# USB_Connectors.net
KiCad netlist of a schematic drawn in Altium Designer
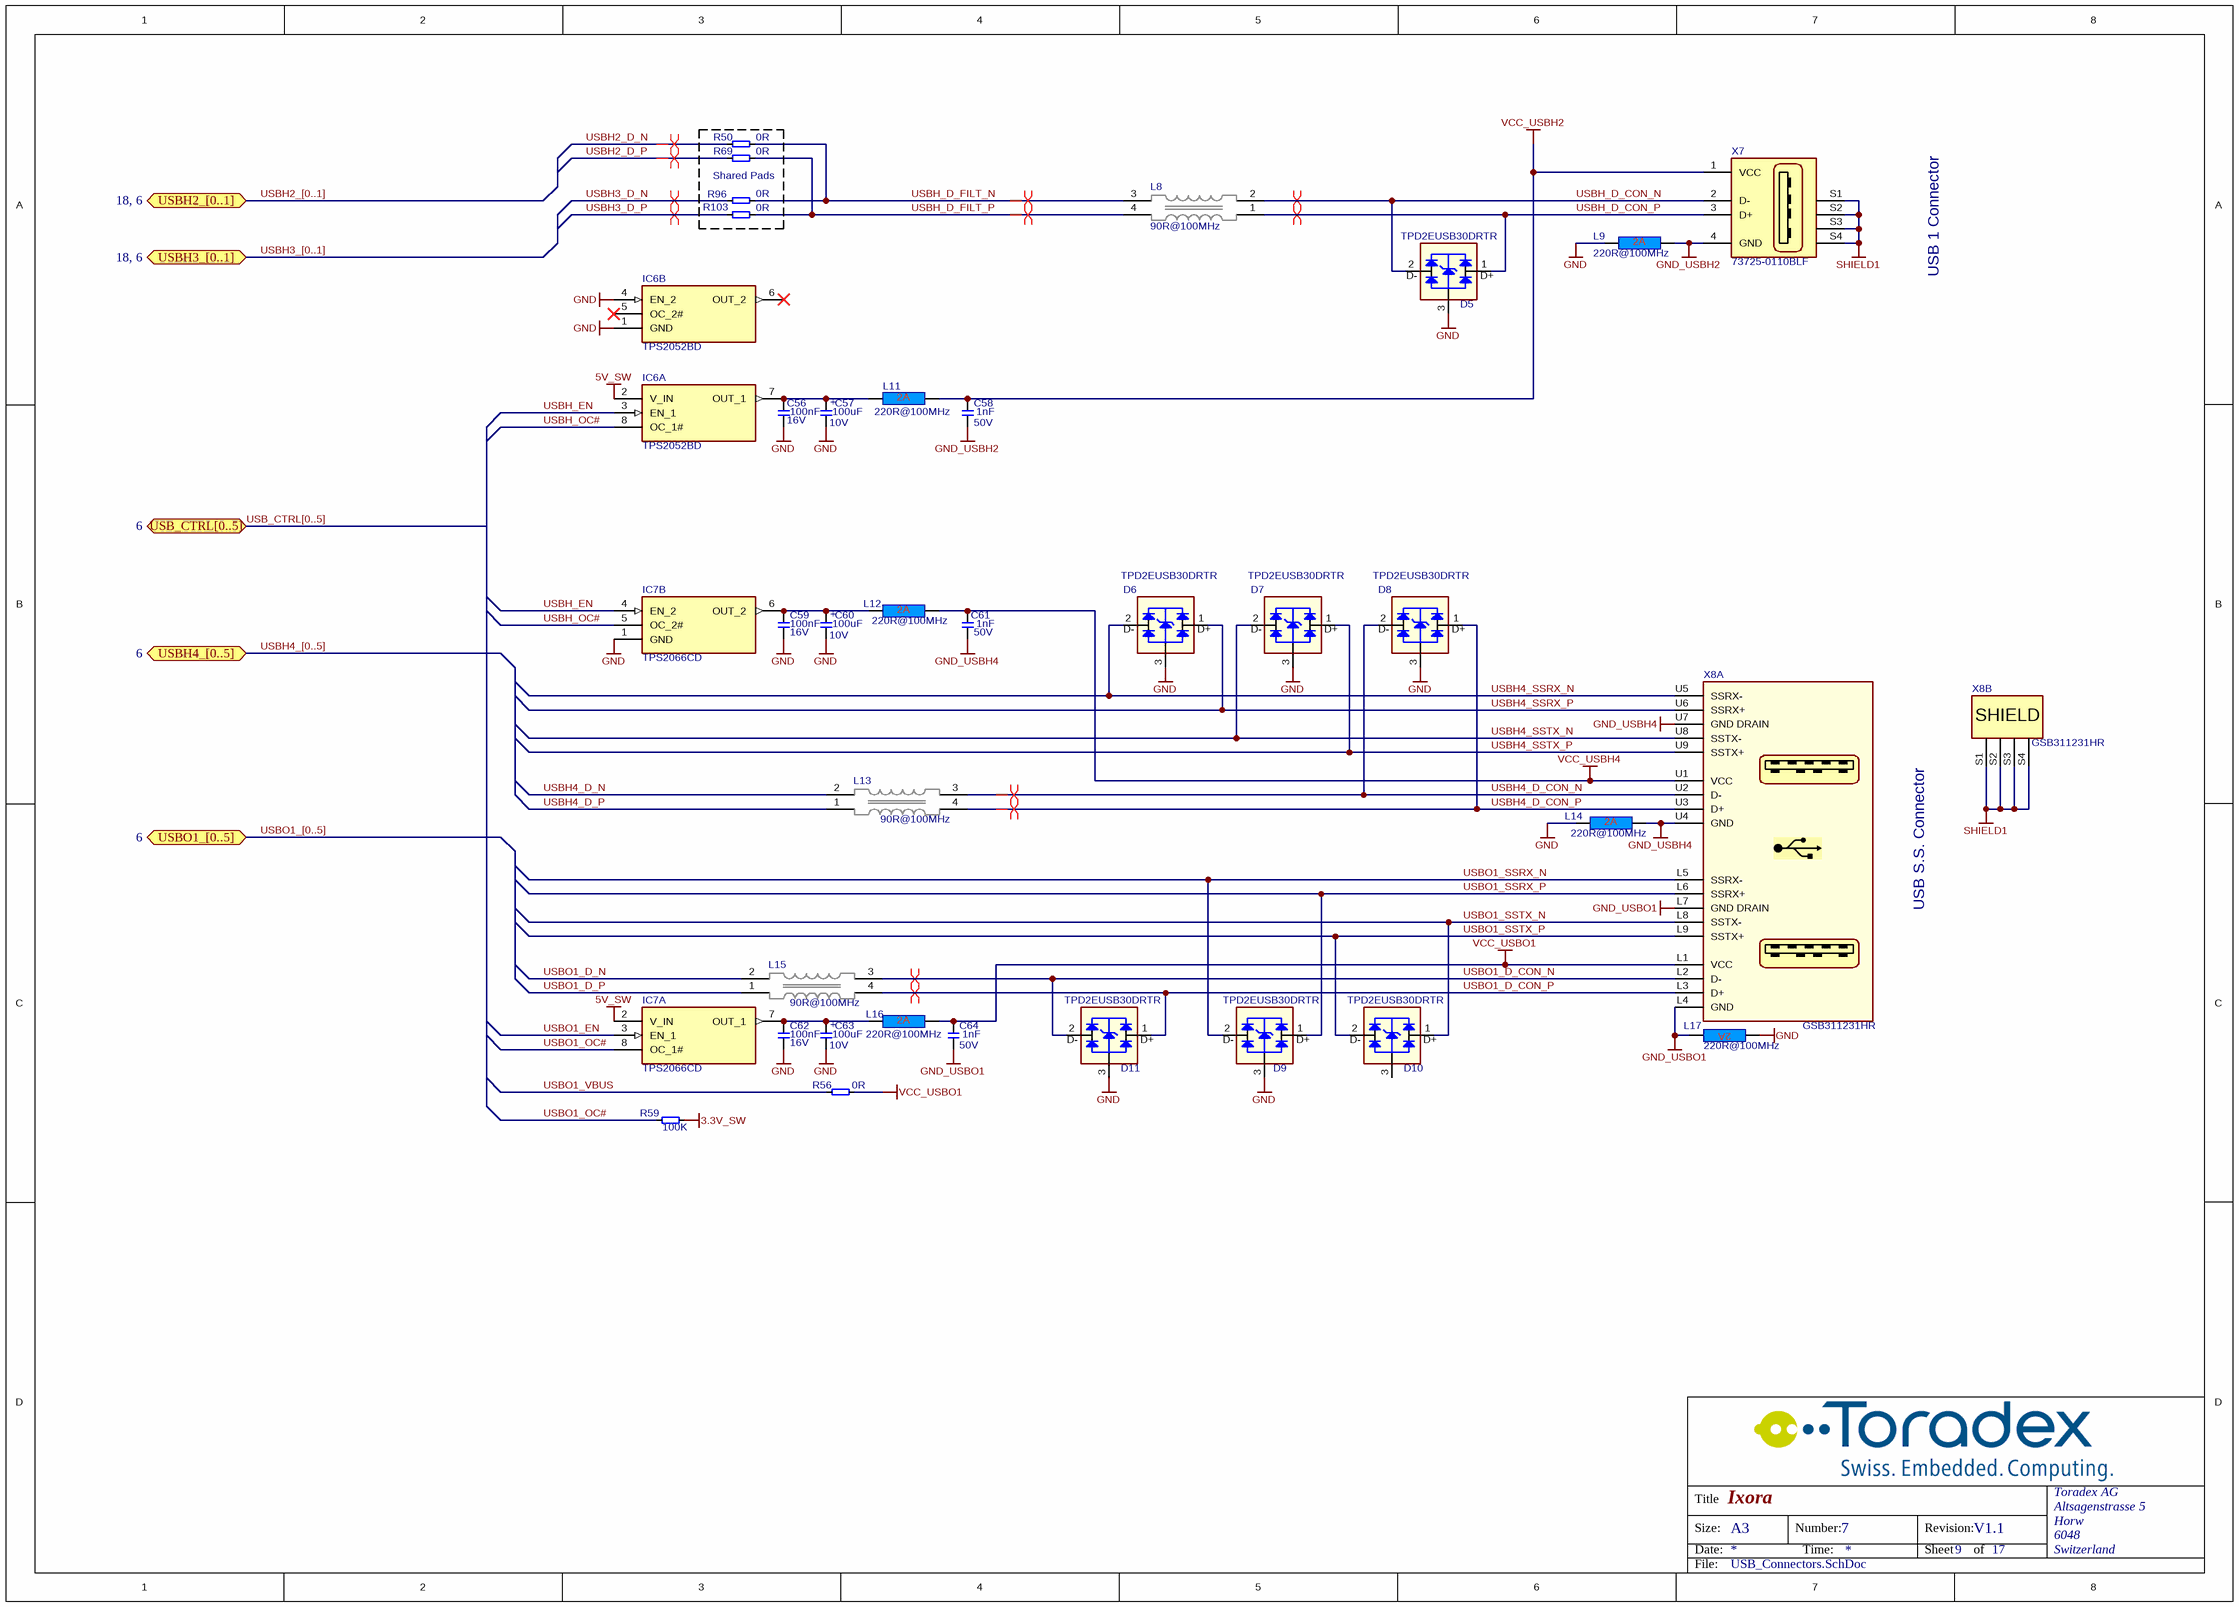
[diagram p0: USB_Connectors.SchDoc]

(export (version "E")
  (design (tool "Eeschema 10.0.6"))
  (components
    (comp (ref "C56")
      (value "100nF")
      (footprint "CAPC1005X60N")
      (description "Capacitor Ceramic X7R 100nF 16V 10% 0402")
      (fields (field (name "TOLERANCE") "10%") (field (name "RATING") "16V"))
      (libsource (lib "Ixora") (part "C-X7R-100nF-16V-10%-0402"))
    )
    (comp (ref "C57")
      (value "100uF")
      (footprint "CAPMP6032X280N")
      (description "Capacitor TA 100uF 10V 10% 6032")
      (fields (field (name "TOLERANCE") "10%") (field (name "RATING") "10V"))
      (libsource (lib "Ixora") (part "C-TA-100uF-10V-10%-6032"))
    )
    (comp (ref "C58")
      (value "1nF")
      (footprint "CAPC1005X60N")
      (description "Capacitor Ceramic X7R 1nF 50V 10% 0402")
      (fields (field (name "TOLERANCE") "10%") (field (name "RATING") "50V"))
      (libsource (lib "Ixora") (part "C-X7R-1nF-50V-10%-0402"))
    )
    (comp (ref "C59")
      (value "100nF")
      (footprint "CAPC1005X60N")
      (description "Capacitor Ceramic X7R 100nF 16V 10% 0402")
      (fields (field (name "TOLERANCE") "10%") (field (name "RATING") "16V"))
      (libsource (lib "Ixora") (part "C-X7R-100nF-16V-10%-0402"))
    )
    (comp (ref "C60")
      (value "100uF")
      (footprint "CAPMP6032X280N")
      (description "Capacitor TA 100uF 10V 10% 6032")
      (fields (field (name "TOLERANCE") "10%") (field (name "RATING") "10V"))
      (libsource (lib "Ixora") (part "C-TA-100uF-10V-10%-6032"))
    )
    (comp (ref "C61")
      (value "1nF")
      (footprint "CAPC1005X60N")
      (description "Capacitor Ceramic X7R 1nF 50V 10% 0402")
      (fields (field (name "TOLERANCE") "10%") (field (name "RATING") "50V"))
      (libsource (lib "Ixora") (part "C-X7R-1nF-50V-10%-0402"))
    )
    (comp (ref "C62")
      (value "100nF")
      (footprint "CAPC1005X60N")
      (description "Capacitor Ceramic X7R 100nF 16V 10% 0402")
      (fields (field (name "TOLERANCE") "10%") (field (name "RATING") "16V"))
      (libsource (lib "Ixora") (part "C-X7R-100nF-16V-10%-0402"))
    )
    (comp (ref "C63")
      (value "100uF")
      (footprint "CAPMP6032X280N")
      (description "Capacitor TA 100uF 10V 10% 6032")
      (fields (field (name "TOLERANCE") "10%") (field (name "RATING") "10V"))
      (libsource (lib "Ixora") (part "C-TA-100uF-10V-10%-6032"))
    )
    (comp (ref "C64")
      (value "1nF")
      (footprint "CAPC1005X60N")
      (description "Capacitor Ceramic X7R 1nF 50V 10% 0402")
      (fields (field (name "TOLERANCE") "10%") (field (name "RATING") "50V"))
      (libsource (lib "Ixora") (part "C-X7R-1nF-50V-10%-0402"))
    )
    (comp (ref "D5")
      (value "TPD2EUSB30DRTR")
      (footprint "T_TI_TPD2EUSB30DRTR")
      (description "2 Channel Protection for Super Speed USB3.0")
      (fields (field (name "MANUFACTURER PART NO.") "TPD2EUSB30DRTR"))
      (libsource (lib "") (part "D-TI-TPD2EUSB30DRTR_1"))
    )
    (comp (ref "D6")
      (value "TPD2EUSB30DRTR")
      (footprint "T_TI_TPD2EUSB30DRTR")
      (description "2 Channel Protection for Super Speed USB3.0")
      (fields (field (name "MANUFACTURER PART NO.") "TPD2EUSB30DRTR"))
      (libsource (lib "") (part "D-TI-TPD2EUSB30DRTR_1"))
    )
    (comp (ref "D7")
      (value "TPD2EUSB30DRTR")
      (footprint "T_TI_TPD2EUSB30DRTR")
      (description "2 Channel Protection for Super Speed USB3.0")
      (fields (field (name "MANUFACTURER PART NO.") "TPD2EUSB30DRTR"))
      (libsource (lib "") (part "D-TI-TPD2EUSB30DRTR_1"))
    )
    (comp (ref "D8")
      (value "TPD2EUSB30DRTR")
      (footprint "T_TI_TPD2EUSB30DRTR")
      (description "2 Channel Protection for Super Speed USB3.0")
      (fields (field (name "MANUFACTURER PART NO.") "TPD2EUSB30DRTR"))
      (libsource (lib "Ixora") (part "D-TI-TPD2EUSB30DRTR"))
    )
    (comp (ref "D9")
      (value "TPD2EUSB30DRTR")
      (footprint "T_TI_TPD2EUSB30DRTR")
      (description "2 Channel Protection for Super Speed USB3.0")
      (fields (field (name "MANUFACTURER PART NO.") "TPD2EUSB30DRTR"))
      (libsource (lib "") (part "D-TI-TPD2EUSB30DRTR_1"))
    )
    (comp (ref "D10")
      (value "TPD2EUSB30DRTR")
      (footprint "T_TI_TPD2EUSB30DRTR")
      (description "2 Channel Protection for Super Speed USB3.0")
      (fields (field (name "MANUFACTURER PART NO.") "TPD2EUSB30DRTR"))
      (libsource (lib "") (part "D-TI-TPD2EUSB30DRTR_2"))
    )
    (comp (ref "D11")
      (value "TPD2EUSB30DRTR")
      (footprint "T_TI_TPD2EUSB30DRTR")
      (description "2 Channel Protection for Super Speed USB3.0")
      (fields (field (name "MANUFACTURER PART NO.") "TPD2EUSB30DRTR"))
      (libsource (lib "") (part "D-TI-TPD2EUSB30DRTR_1"))
    )
    (comp (ref "IC6")
      (value "TPS2052BD")
      (footprint "SOIC127P600X173-8N")
      (description "Dual High Side Switch With OC_DET 500mA/CH")
      (fields (field (name "MANUFACTURER PART NO.") "TPS2052BD"))
      (libsource (lib "Ixora") (part "IC-TI-TPS2052BD"))
    )
    (comp (ref "IC7")
      (value "TPS2066CD")
      (footprint "SOIC127P600X173-8N")
      (description "1A Dual High Side Switch (Current Limiting (Fixed), Over Temperature, Reverse Current, UVLO)")
      (fields (field (name "MANUFACTURER PART NO.") "TPS2066CD"))
      (libsource (lib "Ixora") (part "IC-TI-TPS2066CD"))
    )
    (comp (ref "L8")
      (value "90R@100MHz")
      (footprint "T_Murata_DLW21SN900SQ2")
      (description "Common Mode Choke High Speed 90R 330mA")
      (fields (field (name "TOLERANCE") "25%") (field (name "MANUFACTURER PART NO.") "DLW21SN900SQ2"))
      (libsource (lib "") (part "L-Murata-DLW21SN900SQ2-90R@100MHz-330mA-25%_1"))
    )
    (comp (ref "L9")
      (value "220R@100MHz")
      (footprint "INDC1608X95N")
      (description "220R@100MHz 2A EMI FILTER")
      (fields (field (name "TOLERANCE") "25%"))
      (libsource (lib "Ixora") (part "L-220R@100MHz-2A-25%-0603"))
    )
    (comp (ref "L11")
      (value "220R@100MHz")
      (footprint "INDC1608X95N")
      (description "220R@100MHz 2A EMI FILTER")
      (fields (field (name "TOLERANCE") "25%"))
      (libsource (lib "Ixora") (part "L-220R@100MHz-2A-25%-0603"))
    )
    (comp (ref "L12")
      (value "220R@100MHz")
      (footprint "INDC1608X95N")
      (description "220R@100MHz 2A EMI FILTER")
      (fields (field (name "TOLERANCE") "25%"))
      (libsource (lib "Ixora") (part "L-220R@100MHz-2A-25%-0603"))
    )
    (comp (ref "L13")
      (value "90R@100MHz")
      (footprint "T_Murata_DLW21SN900SQ2")
      (description "Common Mode Choke High Speed 90R 330mA")
      (fields (field (name "TOLERANCE") "25%") (field (name "MANUFACTURER PART NO.") "DLW21SN900SQ2"))
      (libsource (lib "Ixora") (part "L-Murata-DLW21SN900SQ2-90R@100MHz-330mA-25%"))
    )
    (comp (ref "L14")
      (value "220R@100MHz")
      (footprint "INDC1608X95N")
      (description "220R@100MHz 2A EMI FILTER")
      (fields (field (name "TOLERANCE") "25%"))
      (libsource (lib "Ixora") (part "L-220R@100MHz-2A-25%-0603"))
    )
    (comp (ref "L15")
      (value "90R@100MHz")
      (footprint "T_Murata_DLW21SN900SQ2")
      (description "Common Mode Choke High Speed 90R 330mA")
      (fields (field (name "TOLERANCE") "25%") (field (name "MANUFACTURER PART NO.") "DLW21SN900SQ2"))
      (libsource (lib "Ixora") (part "L-Murata-DLW21SN900SQ2-90R@100MHz-330mA-25%"))
    )
    (comp (ref "L16")
      (value "220R@100MHz")
      (footprint "INDC1608X95N")
      (description "220R@100MHz 2A EMI FILTER")
      (fields (field (name "TOLERANCE") "25%"))
      (libsource (lib "Ixora") (part "L-220R@100MHz-2A-25%-0603"))
    )
    (comp (ref "L17")
      (value "220R@100MHz")
      (footprint "INDC1608X95N")
      (description "220R@100MHz 2A EMI FILTER")
      (fields (field (name "TOLERANCE") "25%"))
      (libsource (lib "") (part "L-220R@100MHz-2A-25%-0603_1"))
    )
    (comp (ref "R50")
      (value "0R")
      (footprint "T_RESC0603X30N")
      (description "Resistor 0 ohm 63mW 1% 0603")
      (fields (field (name "TOLERANCE") "1%"))
      (libsource (lib "Ixora") (part "R-0R-63mW-1%-0603"))
    )
    (comp (ref "R56")
      (value "0R")
      (footprint "RESC1005X40N")
      (description "Resistor 0 ohm 63mW 1% 0402")
      (fields (field (name "TOLERANCE") "1%"))
      (libsource (lib "Ixora") (part "R-0R-63mW-1%-0402"))
    )
    (comp (ref "R59")
      (value "100K")
      (footprint "RESC1005X40N")
      (description "Resistor 100 Kohm 63mW 5% 0402")
      (fields (field (name "TOLERANCE") "5%"))
      (libsource (lib "Ixora") (part "R-100KR-63mW-5%-0402"))
    )
    (comp (ref "R69")
      (value "0R")
      (footprint "T_RESC0603X30N")
      (description "Resistor 0 ohm 63mW 1% 0603")
      (fields (field (name "TOLERANCE") "1%"))
      (libsource (lib "Ixora") (part "R-0R-63mW-1%-0603"))
    )
    (comp (ref "R96")
      (value "0R")
      (footprint "T_RESC0603X30N")
      (description "Resistor 0 ohm 63mW 1% 0603")
      (fields (field (name "TOLERANCE") "1%"))
      (libsource (lib "Ixora") (part "R-0R-63mW-1%-0603"))
    )
    (comp (ref "R103")
      (value "0R")
      (footprint "T_RESC0603X30N")
      (description "Resistor 0 ohm 63mW 1% 0603")
      (fields (field (name "TOLERANCE") "1%"))
      (libsource (lib "Ixora") (part "R-0R-63mW-1%-0603"))
    )
    (comp (ref "X7")
      (value "CON-Fci-73725-0110BLF")
      (footprint "T_FCI_73725-0110BLF")
      (description "USB Type A Connector")
      (fields (field (name "MANUFACTURER PART NO.") "73725-0110BLF"))
      (libsource (lib "Ixora") (part "CON-Fci-73725-0110BLF"))
    )
    (comp (ref "X8")
      (value "GSB311231HR")
      (footprint "T_AMPHENOL_ GSB311231HR")
      (description "USB 3.0 double row, Type A")
      (fields (field (name "MANUFACTURER PART NO.") "GSB311231HR"))
      (libsource (lib "Ixora") (part "CON-Amphenol-GSB311231HR"))
    )
  )
  (nets
    (net (code "23") (name "/USBH2_D_N") (class "Default")
      (node (ref "R50") (pin "1") (pinfunction "1_1") (pintype "passive"))
    )
    (net (code "24") (name "/USBH2_D_P") (class "Default")
      (node (ref "R69") (pin "1") (pinfunction "1_1") (pintype "passive"))
    )
    (net (code "26") (name "/USBH3_D_N") (class "Default")
      (node (ref "R96") (pin "1") (pinfunction "1_1") (pintype "passive"))
    )
    (net (code "27") (name "/USBH3_D_P") (class "Default")
      (node (ref "R103") (pin "1") (pinfunction "1_1") (pintype "passive"))
    )
    (net (code "29") (name "/USBH4_D_CON_N") (class "Default")
      (node (ref "D8") (pin "2") (pinfunction "D-_2") (pintype "power_in"))
      (node (ref "L13") (pin "3") (pinfunction "3_3") (pintype "passive"))
      (node (ref "X8") (pin "U2") (pinfunction "D-_U2") (pintype "passive"))
    )
    (net (code "30") (name "/USBH4_D_CON_P") (class "Default")
      (node (ref "D8") (pin "1") (pinfunction "D+_1") (pintype "power_in"))
      (node (ref "L13") (pin "4") (pinfunction "4_4") (pintype "passive"))
      (node (ref "X8") (pin "U3") (pinfunction "D+_U3") (pintype "passive"))
    )
    (net (code "31") (name "/USBH4_D_N") (class "Default")
      (node (ref "L13") (pin "2") (pinfunction "2_2") (pintype "passive"))
    )
    (net (code "32") (name "/USBH4_D_P") (class "Default")
      (node (ref "L13") (pin "1") (pinfunction "1_1") (pintype "passive"))
    )
    (net (code "33") (name "/USBH4_SSRX_N") (class "Default")
      (node (ref "D6") (pin "2") (pinfunction "D-_2") (pintype "power_in"))
      (node (ref "X8") (pin "U5") (pinfunction "SSRX-_U5") (pintype "power_in"))
    )
    (net (code "34") (name "/USBH4_SSRX_P") (class "Default")
      (node (ref "D6") (pin "1") (pinfunction "D+_1") (pintype "power_in"))
      (node (ref "X8") (pin "U6") (pinfunction "SSRX+_U6") (pintype "power_in"))
    )
    (net (code "35") (name "/USBH4_SSTX_N") (class "Default")
      (node (ref "D7") (pin "2") (pinfunction "D-_2") (pintype "power_in"))
      (node (ref "X8") (pin "U8") (pinfunction "SSTX-_U8") (pintype "power_in"))
    )
    (net (code "36") (name "/USBH4_SSTX_P") (class "Default")
      (node (ref "D7") (pin "1") (pinfunction "D+_1") (pintype "power_in"))
      (node (ref "X8") (pin "U9") (pinfunction "SSTX+_U9") (pintype "power_in"))
    )
    (net (code "38") (name "/USBH_D_CON_N") (class "Default")
      (node (ref "D5") (pin "2") (pinfunction "D-_2") (pintype "power_in"))
      (node (ref "L8") (pin "2") (pinfunction "2_2") (pintype "passive"))
      (node (ref "X7") (pin "2") (pinfunction "D-_2") (pintype "passive"))
    )
    (net (code "39") (name "/USBH_D_CON_P") (class "Default")
      (node (ref "D5") (pin "1") (pinfunction "D+_1") (pintype "power_in"))
      (node (ref "L8") (pin "1") (pinfunction "1_1") (pintype "passive"))
      (node (ref "X7") (pin "3") (pinfunction "D+_3") (pintype "passive"))
    )
    (net (code "40") (name "/USBH_D_FILT_N") (class "Default")
      (node (ref "L8") (pin "3") (pinfunction "3_3") (pintype "passive"))
      (node (ref "R50") (pin "2") (pinfunction "2_2") (pintype "passive"))
      (node (ref "R96") (pin "2") (pinfunction "2_2") (pintype "passive"))
    )
    (net (code "41") (name "/USBH_D_FILT_P") (class "Default")
      (node (ref "L8") (pin "4") (pinfunction "4_4") (pintype "passive"))
      (node (ref "R103") (pin "2") (pinfunction "2_2") (pintype "passive"))
      (node (ref "R69") (pin "2") (pinfunction "2_2") (pintype "passive"))
    )
    (net (code "42") (name "/USBH_EN") (class "Default")
      (node (ref "IC6") (pin "3") (pinfunction "EN_1_3") (pintype "input"))
      (node (ref "IC7") (pin "4") (pinfunction "EN_2_4") (pintype "input"))
    )
    (net (code "43") (name "/USBH_OC#") (class "Default")
      (node (ref "IC6") (pin "8") (pinfunction "OC_1#_8") (pintype "passive"))
      (node (ref "IC7") (pin "5") (pinfunction "OC_2#_5") (pintype "passive"))
    )
    (net (code "44") (name "/USBO1_D_CON_N") (class "Default")
      (node (ref "D11") (pin "2") (pinfunction "D-_2") (pintype "power_in"))
      (node (ref "L15") (pin "3") (pinfunction "3_3") (pintype "passive"))
      (node (ref "X8") (pin "L2") (pinfunction "D-_L2") (pintype "passive"))
    )
    (net (code "45") (name "/USBO1_D_CON_P") (class "Default")
      (node (ref "D11") (pin "1") (pinfunction "D+_1") (pintype "power_in"))
      (node (ref "L15") (pin "4") (pinfunction "4_4") (pintype "passive"))
      (node (ref "X8") (pin "L3") (pinfunction "D+_L3") (pintype "passive"))
    )
    (net (code "46") (name "/USBO1_D_N") (class "Default")
      (node (ref "L15") (pin "2") (pinfunction "2_2") (pintype "passive"))
    )
    (net (code "47") (name "/USBO1_D_P") (class "Default")
      (node (ref "L15") (pin "1") (pinfunction "1_1") (pintype "passive"))
    )
    (net (code "48") (name "/USBO1_EN") (class "Default")
      (node (ref "IC7") (pin "3") (pinfunction "EN_1_3") (pintype "input"))
    )
    (net (code "49") (name "/USBO1_OC#") (class "Default")
      (node (ref "IC7") (pin "8") (pinfunction "OC_1#_8") (pintype "passive"))
      (node (ref "R59") (pin "1") (pinfunction "1_1") (pintype "passive"))
    )
    (net (code "50") (name "/USBO1_SSRX_N") (class "Default")
      (node (ref "D9") (pin "2") (pinfunction "D-_2") (pintype "power_in"))
      (node (ref "X8") (pin "L5") (pinfunction "SSRX-_L5") (pintype "power_in"))
    )
    (net (code "51") (name "/USBO1_SSRX_P") (class "Default")
      (node (ref "D9") (pin "1") (pinfunction "D+_1") (pintype "power_in"))
      (node (ref "X8") (pin "L6") (pinfunction "SSRX+_L6") (pintype "power_in"))
    )
    (net (code "52") (name "/USBO1_SSTX_N") (class "Default")
      (node (ref "D10") (pin "1") (pinfunction "D+_1") (pintype "power_in"))
      (node (ref "X8") (pin "L8") (pinfunction "SSTX-_L8") (pintype "power_in"))
    )
    (net (code "53") (name "/USBO1_SSTX_P") (class "Default")
      (node (ref "D10") (pin "2") (pinfunction "D-_2") (pintype "power_in"))
      (node (ref "X8") (pin "L9") (pinfunction "SSTX+_L9") (pintype "power_in"))
    )
    (net (code "54") (name "/USBO1_VBUS") (class "Default")
      (node (ref "R56") (pin "1") (pinfunction "1_1") (pintype "passive"))
    )
    (net (code "57") (name "3.3V_SW") (class "Default")
      (node (ref "R59") (pin "2") (pinfunction "2_2") (pintype "passive"))
    )
    (net (code "58") (name "5V_SW") (class "Default")
      (node (ref "IC6") (pin "2") (pinfunction "V_IN_2") (pintype "power_in"))
      (node (ref "IC7") (pin "2") (pinfunction "V_IN_2") (pintype "power_in"))
    )
    (net (code "59") (name "GND") (class "Default")
      (node (ref "C56") (pin "1") (pinfunction "1_1") (pintype "passive"))
      (node (ref "C57") (pin "2") (pinfunction "2_2") (pintype "passive"))
      (node (ref "C59") (pin "1") (pinfunction "1_1") (pintype "passive"))
      (node (ref "C60") (pin "2") (pinfunction "2_2") (pintype "passive"))
      (node (ref "C62") (pin "1") (pinfunction "1_1") (pintype "passive"))
      (node (ref "C63") (pin "2") (pinfunction "2_2") (pintype "passive"))
      (node (ref "D11") (pin "3") (pinfunction "3_3") (pintype "power_in"))
      (node (ref "D5") (pin "3") (pinfunction "3_3") (pintype "power_in"))
      (node (ref "D6") (pin "3") (pinfunction "3_3") (pintype "power_in"))
      (node (ref "D7") (pin "3") (pinfunction "3_3") (pintype "power_in"))
      (node (ref "D8") (pin "3") (pinfunction "3_3") (pintype "power_in"))
      (node (ref "D9") (pin "3") (pinfunction "3_3") (pintype "power_in"))
      (node (ref "IC6") (pin "1") (pinfunction "GND_1") (pintype "power_in"))
      (node (ref "IC6") (pin "4") (pinfunction "EN_2_4") (pintype "input"))
      (node (ref "IC7") (pin "1") (pinfunction "GND_1") (pintype "power_in"))
      (node (ref "L14") (pin "1") (pinfunction "1_1") (pintype "passive"))
      (node (ref "L17") (pin "1") (pinfunction "1_1") (pintype "passive"))
      (node (ref "L9") (pin "1") (pinfunction "1_1") (pintype "passive"))
    )
    (net (code "60") (name "GND_USBH2") (class "Default")
      (node (ref "C58") (pin "1") (pinfunction "1_1") (pintype "passive"))
      (node (ref "L9") (pin "2") (pinfunction "2_2") (pintype "passive"))
      (node (ref "X7") (pin "4") (pinfunction "GND_4") (pintype "power_in"))
    )
    (net (code "61") (name "GND_USBH4") (class "Default")
      (node (ref "C61") (pin "1") (pinfunction "1_1") (pintype "passive"))
      (node (ref "L14") (pin "2") (pinfunction "2_2") (pintype "passive"))
      (node (ref "X8") (pin "U4") (pinfunction "GND_U4") (pintype "power_in"))
      (node (ref "X8") (pin "U7") (pinfunction "GND_DRAIN_U7") (pintype "power_in"))
    )
    (net (code "62") (name "GND_USBO1") (class "Default")
      (node (ref "C64") (pin "1") (pinfunction "1_1") (pintype "passive"))
      (node (ref "L17") (pin "2") (pinfunction "2_2") (pintype "passive"))
      (node (ref "X8") (pin "L4") (pinfunction "GND_L4") (pintype "power_in"))
      (node (ref "X8") (pin "L7") (pinfunction "GND_DRAIN_L7") (pintype "power_in"))
    )
    (net (code "63") (name "Net-(IC6A-OUT_1)") (class "Default")
      (node (ref "C56") (pin "2") (pinfunction "2_2") (pintype "passive"))
      (node (ref "C57") (pin "1") (pinfunction "1_1") (pintype "passive"))
      (node (ref "IC6") (pin "7") (pinfunction "OUT_1_7") (pintype "output"))
      (node (ref "L11") (pin "1") (pinfunction "1_1") (pintype "passive"))
    )
    (net (code "64") (name "Net-(IC7A-OUT_1)") (class "Default")
      (node (ref "C62") (pin "2") (pinfunction "2_2") (pintype "passive"))
      (node (ref "C63") (pin "1") (pinfunction "1_1") (pintype "passive"))
      (node (ref "IC7") (pin "7") (pinfunction "OUT_1_7") (pintype "output"))
      (node (ref "L16") (pin "1") (pinfunction "1_1") (pintype "passive"))
    )
    (net (code "65") (name "Net-(IC7B-OUT_2)") (class "Default")
      (node (ref "C59") (pin "2") (pinfunction "2_2") (pintype "passive"))
      (node (ref "C60") (pin "1") (pinfunction "1_1") (pintype "passive"))
      (node (ref "IC7") (pin "6") (pinfunction "OUT_2_6") (pintype "output"))
      (node (ref "L12") (pin "1") (pinfunction "1_1") (pintype "passive"))
    )
    (net (code "66") (name "SHIELD1") (class "Default")
      (node (ref "X7") (pin "S1") (pinfunction "S1_S1") (pintype "passive"))
      (node (ref "X7") (pin "S2") (pinfunction "S2_S2") (pintype "passive"))
      (node (ref "X7") (pin "S3") (pinfunction "S3_S3") (pintype "passive"))
      (node (ref "X7") (pin "S4") (pinfunction "S4_S4") (pintype "passive"))
      (node (ref "X8") (pin "S1") (pinfunction "SHIELD_S1") (pintype "passive"))
      (node (ref "X8") (pin "S2") (pinfunction "SHIELD_S2") (pintype "passive"))
      (node (ref "X8") (pin "S3") (pinfunction "SHIELD_S3") (pintype "passive"))
      (node (ref "X8") (pin "S4") (pinfunction "SHIELD_S4") (pintype "passive"))
    )
    (net (code "67") (name "VCC_USBH2") (class "Default")
      (node (ref "C58") (pin "2") (pinfunction "2_2") (pintype "passive"))
      (node (ref "L11") (pin "2") (pinfunction "2_2") (pintype "passive"))
      (node (ref "X7") (pin "1") (pinfunction "VCC_1") (pintype "power_in"))
    )
    (net (code "68") (name "VCC_USBH4") (class "Default")
      (node (ref "C61") (pin "2") (pinfunction "2_2") (pintype "passive"))
      (node (ref "L12") (pin "2") (pinfunction "2_2") (pintype "passive"))
      (node (ref "X8") (pin "U1") (pinfunction "VCC_U1") (pintype "power_in"))
    )
    (net (code "69") (name "VCC_USBO1") (class "Default")
      (node (ref "C64") (pin "2") (pinfunction "2_2") (pintype "passive"))
      (node (ref "L16") (pin "2") (pinfunction "2_2") (pintype "passive"))
      (node (ref "R56") (pin "2") (pinfunction "2_2") (pintype "passive"))
      (node (ref "X8") (pin "L1") (pinfunction "VCC_L1") (pintype "power_in"))
    )
    (net (code "70") (name "unconnected-(D10-Pad3)") (class "Default")
      (node (ref "D10") (pin "3") (pinfunction "3_3") (pintype "power_in"))
    )
    (net (code "71") (name "unconnected-(IC6B-OC_2#-Pad5)") (class "Default")
      (node (ref "IC6") (pin "5") (pinfunction "OC_2#_5") (pintype "passive+no_connect"))
    )
    (net (code "72") (name "unconnected-(IC6B-OUT_2-Pad6)") (class "Default")
      (node (ref "IC6") (pin "6") (pinfunction "OUT_2_6") (pintype "output+no_connect"))
    )
  )
)
